# 02-MCU.net
KiCad netlist of a schematic drawn in Altium Designer
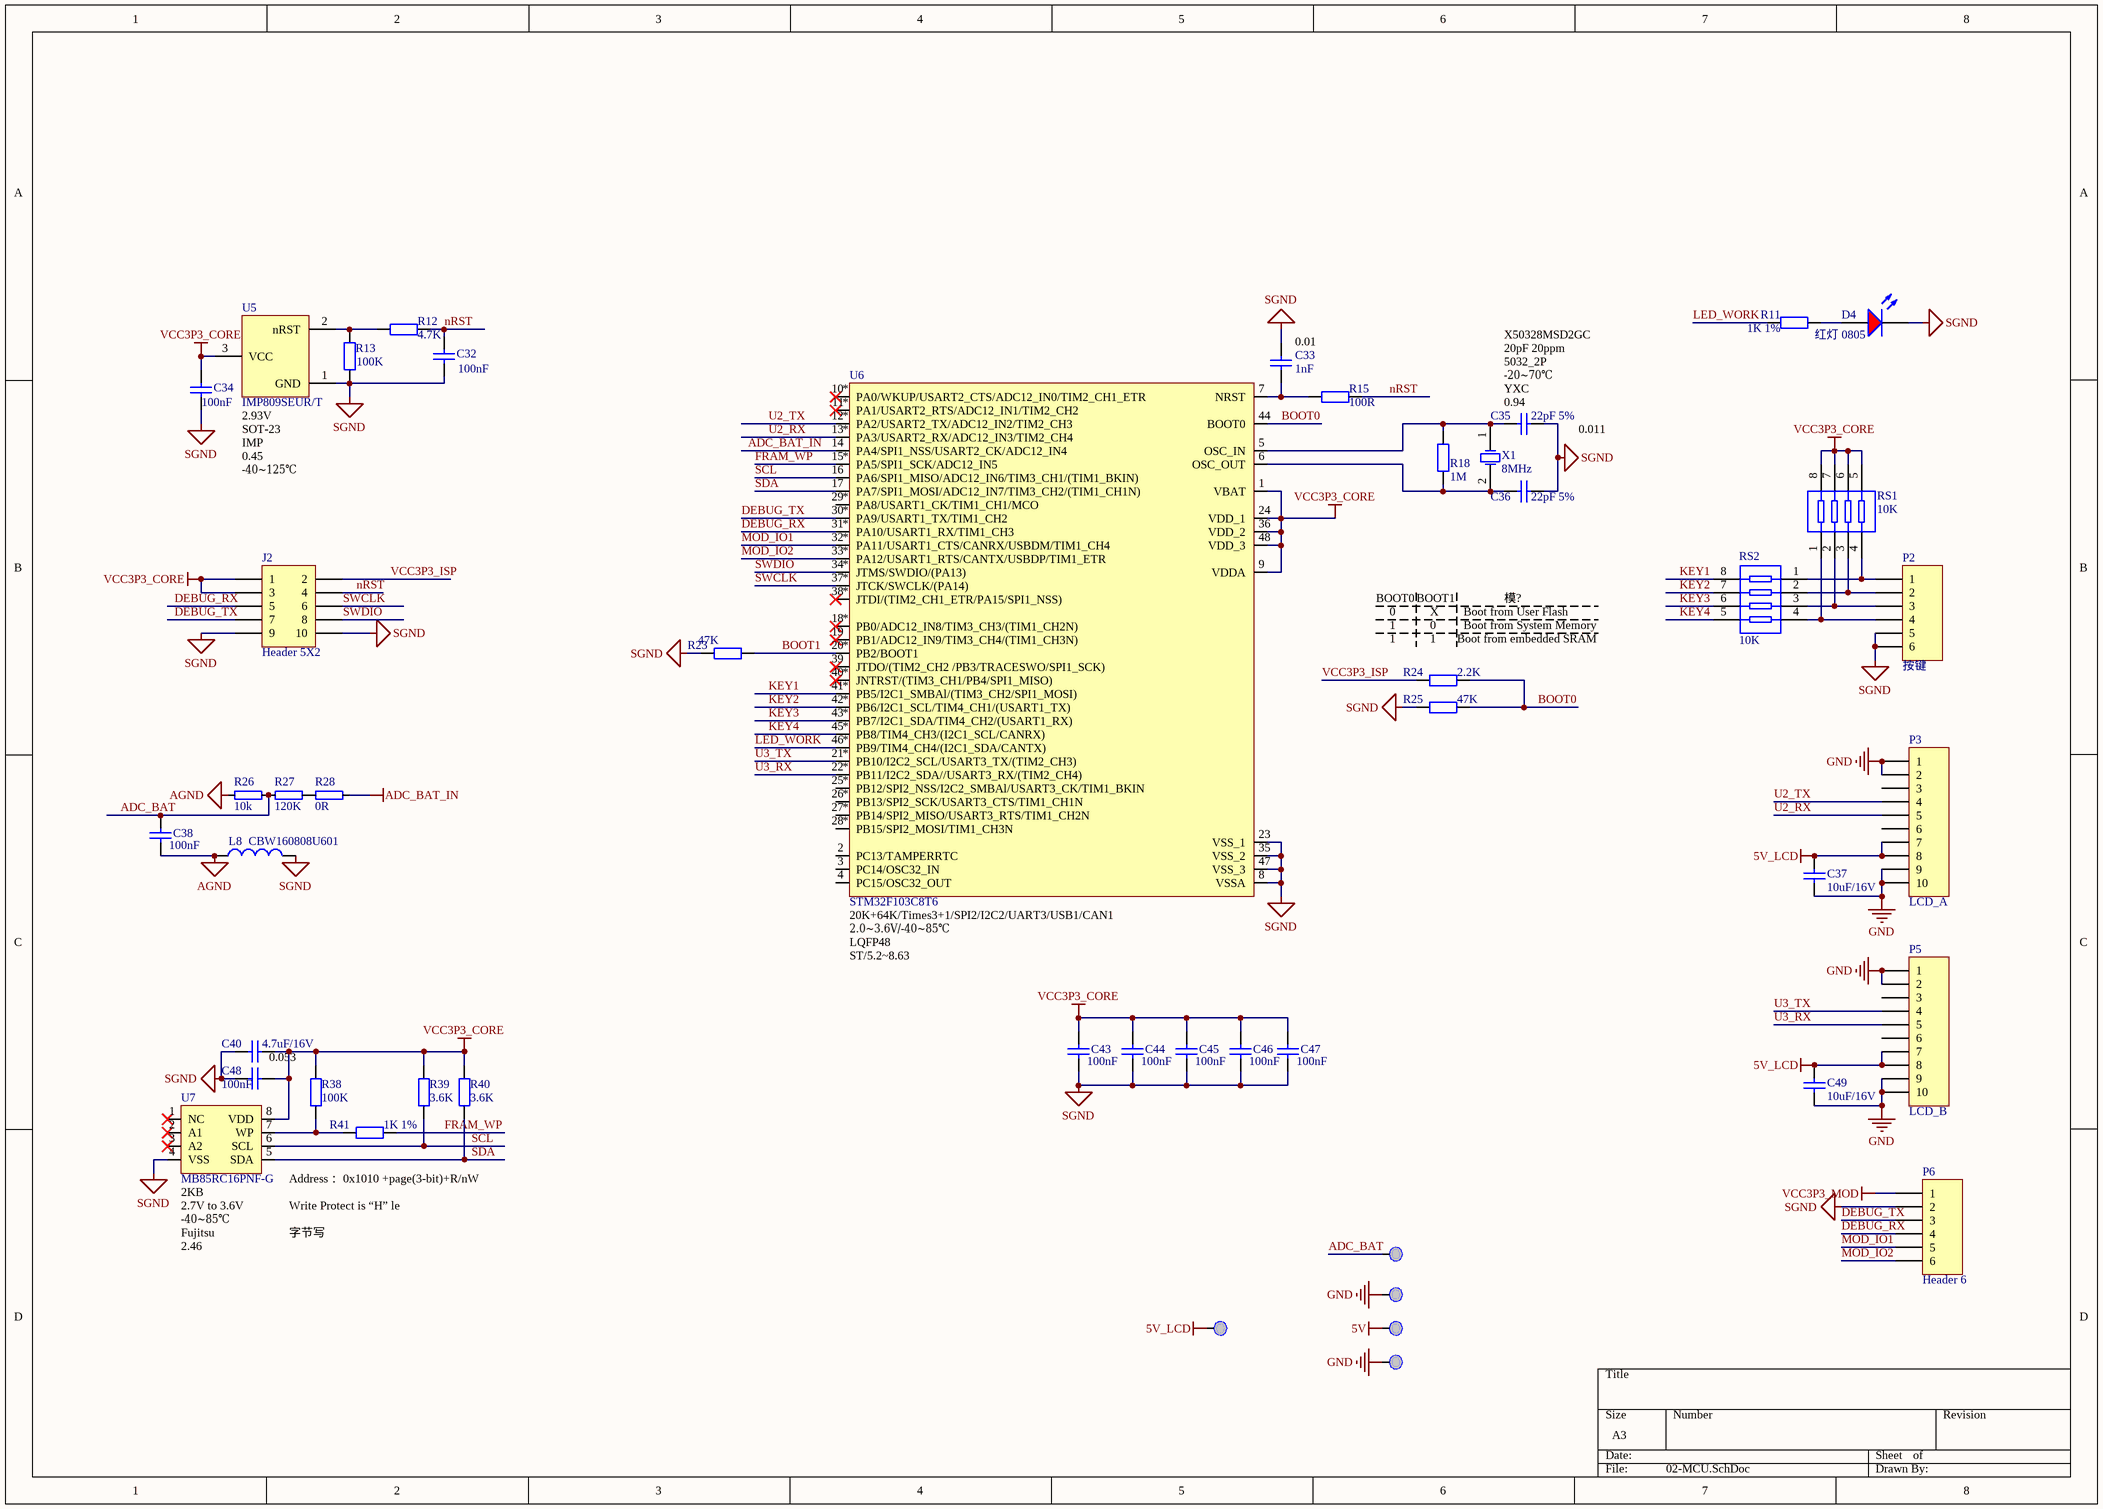
[diagram p0: 02-MCU.SchDoc]

(export (version "E")
  (design (tool "Eeschema 10.0.6"))
  (components
    (comp (ref "C32")
      (value "100nF")
      (footprint "C1608(CC0603)")
      (description "Capacitor")
      (fields (field (name "PUBLISHER") "Altium Limited"))
      (libsource (lib "Miscellaneous Devices") (part "Cap"))
    )
    (comp (ref "C33")
      (value "1nF")
      (footprint "C1608(CC0603)")
      (description "Capacitor")
      (fields (field (name "PUBLISHER") "Altium Limited"))
      (libsource (lib "Miscellaneous Devices") (part "Cap"))
    )
    (comp (ref "C34")
      (value "100nF")
      (footprint "C1608(CC0603)")
      (description "Capacitor")
      (fields (field (name "PUBLISHER") "Altium Limited"))
      (libsource (lib "Miscellaneous Devices") (part "Cap"))
    )
    (comp (ref "C35")
      (value "22pF 5%")
      (footprint "C1608(CC0603)")
      (description "Capacitor")
      (fields (field (name "PUBLISHER") "Altium Limited"))
      (libsource (lib "") (part "Cap_1"))
    )
    (comp (ref "C36")
      (value "22pF 5%")
      (footprint "C1608(CC0603)")
      (description "Capacitor")
      (fields (field (name "PUBLISHER") "Altium Limited"))
      (libsource (lib "") (part "Cap_1"))
    )
    (comp (ref "C37")
      (value "10uF/16V")
      (footprint "C2012(CC0805)")
      (description "Capacitor")
      (fields (field (name "PUBLISHER") "Altium Limited"))
      (libsource (lib "Miscellaneous Devices") (part "Cap"))
    )
    (comp (ref "C38")
      (value "100nF")
      (footprint "C1608(CC0603)")
      (description "Capacitor")
      (fields (field (name "PUBLISHER") "Altium Limited"))
      (libsource (lib "Miscellaneous Devices") (part "Cap"))
    )
    (comp (ref "C40")
      (value "4.7uF/16V")
      (footprint "C1608(CC0603)")
      (description "Capacitor")
      (fields (field (name "PUBLISHER") "Altium Limited"))
      (libsource (lib "Miscellaneous Devices") (part "Cap"))
    )
    (comp (ref "C43")
      (value "100nF")
      (footprint "C1608(CC0603)")
      (description "Capacitor")
      (fields (field (name "PUBLISHER") "Altium Limited"))
      (libsource (lib "Miscellaneous Devices") (part "Cap"))
    )
    (comp (ref "C44")
      (value "100nF")
      (footprint "C1608(CC0603)")
      (description "Capacitor")
      (fields (field (name "PUBLISHER") "Altium Limited"))
      (libsource (lib "Miscellaneous Devices") (part "Cap"))
    )
    (comp (ref "C45")
      (value "100nF")
      (footprint "C1608(CC0603)")
      (description "Capacitor")
      (fields (field (name "PUBLISHER") "Altium Limited"))
      (libsource (lib "Miscellaneous Devices") (part "Cap"))
    )
    (comp (ref "C46")
      (value "100nF")
      (footprint "C1608(CC0603)")
      (description "Capacitor")
      (fields (field (name "PUBLISHER") "Altium Limited"))
      (libsource (lib "Miscellaneous Devices") (part "Cap"))
    )
    (comp (ref "C47")
      (value "100nF")
      (footprint "C1608(CC0603)")
      (description "Capacitor")
      (fields (field (name "PUBLISHER") "Altium Limited"))
      (libsource (lib "Miscellaneous Devices") (part "Cap"))
    )
    (comp (ref "C48")
      (value "100nF")
      (footprint "C1608(CC0603)")
      (description "Capacitor")
      (fields (field (name "PUBLISHER") "Altium Limited"))
      (libsource (lib "") (part "Cap_1"))
    )
    (comp (ref "C49")
      (value "10uF/16V")
      (footprint "C2012(CC0805)")
      (description "Capacitor")
      (fields (field (name "PUBLISHER") "Altium Limited"))
      (libsource (lib "Miscellaneous Devices") (part "Cap"))
    )
    (comp (ref "D4")
      (value "红灯 0805")
      (footprint "LC-0603_LED_S1")
      (description "发光二极管")
      (libsource (lib "Miscellaneous Devices LC") (part "0805 红灯"))
    )
    (comp (ref "J2")
      (value "Header 5X2")
      (footprint "HDR2X5")
      (description "Header, 5-Pin, Dual row")
      (fields (field (name "PUBLISHER") "Altium Limited"))
      (libsource (lib "Miscellaneous Connectors") (part "Header 5X2"))
    )
    (comp (ref "L8")
      (value "CBW160808U601")
      (footprint "C1608(CC0603)")
      (description "Inductor")
      (fields (field (name "PUBLISHER") "Altium Limited"))
      (libsource (lib "Miscellaneous Devices") (part "Inductor"))
    )
    (comp (ref "P2")
      (value "按键")
      (footprint "PH-6A")
      (description "Header, 6-Pin")
      (fields (field (name "PUBLISHER") "Altium Limited"))
      (libsource (lib "Miscellaneous Connectors") (part "Header 6"))
    )
    (comp (ref "P3")
      (value "LCD_A")
      (footprint "2mm-header_SMT")
      (description "Header, 10-Pin")
      (fields (field (name "PUBLISHER") "Altium Limited"))
      (libsource (lib "Miscellaneous Connectors") (part "Header 10"))
    )
    (comp (ref "P5")
      (value "LCD_B")
      (footprint "2mm-header_SMT")
      (description "Header, 10-Pin")
      (fields (field (name "PUBLISHER") "Altium Limited"))
      (libsource (lib "Miscellaneous Connectors") (part "Header 10"))
    )
    (comp (ref "P6")
      (value "Header 6")
      (footprint "HDR1X6")
      (description "Header, 6-Pin")
      (fields (field (name "PUBLISHER") "Altium Limited"))
      (libsource (lib "Miscellaneous Connectors") (part "Header 6"))
    )
    (comp (ref "R11")
      (value "1K 1%")
      (footprint "C1608(CC0603)")
      (description "Resistor")
      (fields (field (name "PUBLISHER") "Altium Limited"))
      (libsource (lib "") (part "Res2_1"))
    )
    (comp (ref "R12")
      (value "4.7K")
      (footprint "C1608(CC0603)")
      (description "Resistor")
      (fields (field (name "PUBLISHER") "Altium Limited"))
      (libsource (lib "") (part "Res2_1"))
    )
    (comp (ref "R13")
      (value "100K")
      (footprint "C1608(CC0603)")
      (description "Resistor")
      (fields (field (name "PUBLISHER") "Altium Limited"))
      (libsource (lib "Miscellaneous Devices") (part "Res2"))
    )
    (comp (ref "R15")
      (value "100R")
      (footprint "C1608(CC0603)")
      (description "Resistor")
      (fields (field (name "PUBLISHER") "Altium Limited"))
      (libsource (lib "") (part "Res2_1"))
    )
    (comp (ref "R18")
      (value "1M")
      (footprint "C1608(CC0603)")
      (description "Resistor")
      (fields (field (name "PUBLISHER") "Altium Limited"))
      (libsource (lib "") (part "Res2_2"))
    )
    (comp (ref "R23")
      (value "47K")
      (footprint "C1608(CC0603)")
      (description "Resistor")
      (fields (field (name "PUBLISHER") "Altium Limited"))
      (libsource (lib "") (part "Res2_1"))
    )
    (comp (ref "R24")
      (value "2.2K")
      (footprint "C1608(CC0603)")
      (description "Resistor")
      (fields (field (name "PUBLISHER") "Altium Limited"))
      (libsource (lib "") (part "Res2_3"))
    )
    (comp (ref "R25")
      (value "47K")
      (footprint "C1608(CC0603)")
      (description "Resistor")
      (fields (field (name "PUBLISHER") "Altium Limited"))
      (libsource (lib "") (part "Res2_1"))
    )
    (comp (ref "R26") (value "10k") (footprint "C1608(CC0603)") (libsource (lib "SCHS") (part "RES5")))
    (comp (ref "R27") (value "120K") (footprint "C1608(CC0603)") (libsource (lib "SCHS") (part "RES5")))
    (comp (ref "R28") (value "0R") (footprint "C1608(CC0603)") (libsource (lib "SCHS") (part "RES5")))
    (comp (ref "R38")
      (value "100K")
      (footprint "C1608(CC0603)")
      (description "Resistor")
      (fields (field (name "PUBLISHER") "Altium Limited"))
      (libsource (lib "Miscellaneous Devices") (part "Res2"))
    )
    (comp (ref "R39")
      (value "3.6K")
      (footprint "C1608(CC0603)")
      (description "Resistor")
      (fields (field (name "PUBLISHER") "Altium Limited"))
      (libsource (lib "Miscellaneous Devices") (part "Res2"))
    )
    (comp (ref "R40")
      (value "3.6K")
      (footprint "C1608(CC0603)")
      (description "Resistor")
      (fields (field (name "PUBLISHER") "Altium Limited"))
      (libsource (lib "Miscellaneous Devices") (part "Res2"))
    )
    (comp (ref "R41")
      (value "1K 1%")
      (footprint "C1608(CC0603)")
      (description "Resistor")
      (fields (field (name "PUBLISHER") "Altium Limited"))
      (libsource (lib "") (part "Res2_4"))
    )
    (comp (ref "RS1")
      (value "10K")
      (footprint "LC-0603_Rx4")
      (description "贴片排阻")
      (libsource (lib "Miscellaneous Devices LC") (part "0603*4  10KΩ (103) 5%"))
    )
    (comp (ref "RS2")
      (value "10K")
      (footprint "LC-0603_Rx4")
      (description "贴片排阻")
      (libsource (lib "Miscellaneous Devices LC") (part "0603*4  10KΩ (103) 5%"))
    )
    (comp (ref "T13") (value "TP") (footprint "M2铜柱") (libsource (lib "个人") (part "TP")))
    (comp (ref "T15") (value "TP") (footprint "M2铜柱") (libsource (lib "个人") (part "TP")))
    (comp (ref "T16") (value "TP") (footprint "M2铜柱") (libsource (lib "个人") (part "TP")))
    (comp (ref "T18") (value "TP") (footprint "M2铜柱") (libsource (lib "个人") (part "TP")))
    (comp (ref "T20") (value "TP") (footprint "M2铜柱") (libsource (lib "个人") (part "TP")))
    (comp (ref "U5")
      (value "IMP809SEUR/T")
      (footprint "SOT-23")
      (libsource (lib "Schlibsxw") (part "CAT810"))
    )
    (comp (ref "U6")
      (value "STM32F103C8T6")
      (footprint "LC-LQFP-48_7x7x05P")
      (libsource (lib "Schlibsxw") (part "STM32F103Cx"))
    )
    (comp (ref "U7")
      (value "MB85RC16PNF-G")
      (footprint "LC-SOP-8_150mil")
      (libsource (lib "Schlibsxw") (part "FM24CL04"))
    )
    (comp (ref "X1")
      (value "8MHz")
      (footprint "XTAL-5032")
      (description "Crystal Oscillator")
      (fields (field (name "PUBLISHER") "Altium Limited"))
      (libsource (lib "Miscellaneous Devices") (part "XTAL"))
    )
  )
  (nets
    (net (code "1") (name "/ADC_BAT") (class "Default")
      (node (ref "C38") (pin "1") (pinfunction "1_1") (pintype "passive"))
      (node (ref "R26") (pin "1") (pintype "passive"))
      (node (ref "R27") (pin "2") (pintype "passive"))
      (node (ref "T13") (pin "1") (pintype "passive"))
    )
    (net (code "2") (name "/BOOT0") (class "Default")
      (node (ref "R24") (pin "1") (pinfunction "1_1") (pintype "passive"))
      (node (ref "R25") (pin "2") (pinfunction "2_2") (pintype "passive"))
      (node (ref "U6") (pin "44") (pinfunction "BOOT0_44") (pintype "passive"))
    )
    (net (code "3") (name "/BOOT1") (class "Default")
      (node (ref "R23") (pin "2") (pinfunction "2_2") (pintype "passive"))
      (node (ref "U6") (pin "20") (pinfunction "PB2/BOOT1_20") (pintype "passive"))
    )
    (net (code "4") (name "/DEBUG_RX") (class "Default")
      (node (ref "J2") (pin "5") (pinfunction "5_5") (pintype "passive"))
      (node (ref "P6") (pin "4") (pinfunction "4_4") (pintype "passive"))
      (node (ref "U6") (pin "31") (pinfunction "PA10/USART1_RX/TIM1_CH3_31") (pintype "passive"))
    )
    (net (code "5") (name "/DEBUG_TX") (class "Default")
      (node (ref "J2") (pin "7") (pinfunction "7_7") (pintype "passive"))
      (node (ref "P6") (pin "3") (pinfunction "3_3") (pintype "passive"))
      (node (ref "U6") (pin "30") (pinfunction "PA9/USART1_TX/TIM1_CH2_30") (pintype "passive"))
    )
    (net (code "6") (name "/FRAM_WP") (class "Default")
      (node (ref "R41") (pin "2") (pinfunction "2_2") (pintype "passive"))
      (node (ref "U6") (pin "15") (pinfunction "PA5/SPI1_SCK/ADC12_IN5_15") (pintype "passive"))
    )
    (net (code "7") (name "/KEY1") (class "Default")
      (node (ref "RS2") (pin "8") (pinfunction "8_8") (pintype "passive"))
      (node (ref "U6") (pin "41") (pinfunction "PB5/I2C1_SMBAl/(TIM3_CH2/SPI1_MOSI)_41") (pintype "passive"))
    )
    (net (code "8") (name "/KEY2") (class "Default")
      (node (ref "RS2") (pin "7") (pinfunction "7_7") (pintype "passive"))
      (node (ref "U6") (pin "42") (pinfunction "PB6/I2C1_SCL/TIM4_CH1/(USART1_TX)_42") (pintype "passive"))
    )
    (net (code "9") (name "/KEY3") (class "Default")
      (node (ref "RS2") (pin "6") (pinfunction "6_6") (pintype "passive"))
      (node (ref "U6") (pin "43") (pinfunction "PB7/I2C1_SDA/TIM4_CH2/(USART1_RX)_43") (pintype "passive"))
    )
    (net (code "10") (name "/KEY4") (class "Default")
      (node (ref "RS2") (pin "5") (pinfunction "5_5") (pintype "passive"))
      (node (ref "U6") (pin "45") (pinfunction "PB8/TIM4_CH3/(I2C1_SCL/CANRX)_45") (pintype "passive"))
    )
    (net (code "11") (name "/LED_WORK") (class "Default")
      (node (ref "R11") (pin "1") (pinfunction "1_1") (pintype "passive"))
      (node (ref "U6") (pin "46") (pinfunction "PB9/TIM4_CH4/(I2C1_SDA/CANTX)_46") (pintype "passive"))
    )
    (net (code "12") (name "/MOD_IO1") (class "Default")
      (node (ref "P6") (pin "5") (pinfunction "5_5") (pintype "passive"))
      (node (ref "U6") (pin "32") (pinfunction "PA11/USART1_CTS/CANRX/USBDM/TIM1_CH4_32") (pintype "passive"))
    )
    (net (code "13") (name "/MOD_IO2") (class "Default")
      (node (ref "P6") (pin "6") (pinfunction "6_6") (pintype "passive"))
      (node (ref "U6") (pin "33") (pinfunction "PA12/USART1_RTS/CANTX/USBDP/TIM1_ETR_33") (pintype "passive"))
    )
    (net (code "14") (name "/SCL") (class "Default")
      (node (ref "R39") (pin "1") (pinfunction "1_1") (pintype "passive"))
      (node (ref "U6") (pin "16") (pinfunction "PA6/SPI1_MISO/ADC12_IN6/TIM3_CH1/(TIM1_BKIN)_16") (pintype "passive"))
      (node (ref "U7") (pin "6") (pinfunction "SCL_6") (pintype "passive"))
    )
    (net (code "15") (name "/SDA") (class "Default")
      (node (ref "R40") (pin "1") (pinfunction "1_1") (pintype "passive"))
      (node (ref "U6") (pin "17") (pinfunction "PA7/SPI1_MOSI/ADC12_IN7/TIM3_CH2/(TIM1_CH1N)_17") (pintype "passive"))
      (node (ref "U7") (pin "5") (pinfunction "SDA_5") (pintype "passive"))
    )
    (net (code "16") (name "/SWCLK") (class "Default")
      (node (ref "J2") (pin "6") (pinfunction "6_6") (pintype "passive"))
      (node (ref "U6") (pin "37") (pinfunction "JTCK/SWCLK/(PA14)_37") (pintype "passive"))
    )
    (net (code "17") (name "/SWDIO") (class "Default")
      (node (ref "J2") (pin "8") (pinfunction "8_8") (pintype "passive"))
      (node (ref "U6") (pin "34") (pinfunction "JTMS/SWDIO/(PA13)_34") (pintype "passive"))
    )
    (net (code "18") (name "/U2_RX") (class "Default")
      (node (ref "P3") (pin "5") (pinfunction "5_5") (pintype "passive"))
      (node (ref "U6") (pin "13") (pinfunction "PA3/USART2_RX/ADC12_IN3/TIM2_CH4_13") (pintype "passive"))
    )
    (net (code "19") (name "/U2_TX") (class "Default")
      (node (ref "P3") (pin "4") (pinfunction "4_4") (pintype "passive"))
      (node (ref "U6") (pin "12") (pinfunction "PA2/USART2_TX/ADC12_IN2/TIM2_CH3_12") (pintype "passive"))
    )
    (net (code "20") (name "/U3_RX") (class "Default")
      (node (ref "P5") (pin "5") (pinfunction "5_5") (pintype "passive"))
      (node (ref "U6") (pin "22") (pinfunction "PB11/I2C2_SDA//USART3_RX/(TIM2_CH4)_22") (pintype "passive"))
    )
    (net (code "21") (name "/U3_TX") (class "Default")
      (node (ref "P5") (pin "4") (pinfunction "4_4") (pintype "passive"))
      (node (ref "U6") (pin "21") (pinfunction "PB10/I2C2_SCL/USART3_TX/(TIM2_CH3)_21") (pintype "passive"))
    )
    (net (code "22") (name "/VCC3P3_ISP") (class "Default")
      (node (ref "J2") (pin "2") (pinfunction "2_2") (pintype "passive"))
      (node (ref "R24") (pin "2") (pinfunction "2_2") (pintype "passive"))
    )
    (net (code "23") (name "/nRST") (class "Default")
      (node (ref "C32") (pin "1") (pinfunction "1_1") (pintype "passive"))
      (node (ref "J2") (pin "4") (pinfunction "4_4") (pintype "passive"))
      (node (ref "R12") (pin "2") (pinfunction "2_2") (pintype "passive"))
      (node (ref "R15") (pin "2") (pinfunction "2_2") (pintype "passive"))
    )
    (net (code "24") (name "5V") (class "Default") (node (ref "T15") (pin "1") (pintype "passive")))
    (net (code "25") (name "5V_LCD") (class "Default")
      (node (ref "C37") (pin "2") (pinfunction "2_2") (pintype "passive"))
      (node (ref "C49") (pin "2") (pinfunction "2_2") (pintype "passive"))
      (node (ref "P3") (pin "7") (pinfunction "7_7") (pintype "passive"))
      (node (ref "P3") (pin "8") (pinfunction "8_8") (pintype "passive"))
      (node (ref "P5") (pin "7") (pinfunction "7_7") (pintype "passive"))
      (node (ref "P5") (pin "8") (pinfunction "8_8") (pintype "passive"))
      (node (ref "T16") (pin "1") (pintype "passive"))
    )
    (net (code "26") (name "ADC_BAT_IN") (class "Default")
      (node (ref "R28") (pin "1") (pintype "passive"))
      (node (ref "U6") (pin "14") (pinfunction "PA4/SPI1_NSS/USART2_CK/ADC12_IN4_14") (pintype "passive"))
    )
    (net (code "27") (name "AGND") (class "Default")
      (node (ref "C38") (pin "2") (pinfunction "2_2") (pintype "passive"))
      (node (ref "L8") (pin "1") (pinfunction "1_1") (pintype "passive"))
      (node (ref "R26") (pin "2") (pintype "passive"))
    )
    (net (code "28") (name "GND") (class "Default")
      (node (ref "C37") (pin "1") (pinfunction "1_1") (pintype "passive"))
      (node (ref "C49") (pin "1") (pinfunction "1_1") (pintype "passive"))
      (node (ref "P3") (pin "1") (pinfunction "1_1") (pintype "passive"))
      (node (ref "P3") (pin "10") (pinfunction "10_10") (pintype "passive"))
      (node (ref "P3") (pin "2") (pinfunction "2_2") (pintype "passive"))
      (node (ref "P3") (pin "9") (pinfunction "9_9") (pintype "passive"))
      (node (ref "P5") (pin "1") (pinfunction "1_1") (pintype "passive"))
      (node (ref "P5") (pin "10") (pinfunction "10_10") (pintype "passive"))
      (node (ref "P5") (pin "2") (pinfunction "2_2") (pintype "passive"))
      (node (ref "P5") (pin "9") (pinfunction "9_9") (pintype "passive"))
      (node (ref "T18") (pin "1") (pintype "passive"))
      (node (ref "T20") (pin "1") (pintype "passive"))
    )
    (net (code "29") (name "Net-(D4-PadA)") (class "Default")
      (node (ref "D4") (pin "A") (pinfunction "A_A") (pintype "passive"))
      (node (ref "R11") (pin "2") (pinfunction "2_2") (pintype "passive"))
    )
    (net (code "30") (name "Net-(P2-Pad1)") (class "Default")
      (node (ref "P2") (pin "1") (pinfunction "1_1") (pintype "passive"))
      (node (ref "RS1") (pin "4") (pinfunction "4_4") (pintype "passive"))
      (node (ref "RS2") (pin "1") (pinfunction "1_1") (pintype "passive"))
    )
    (net (code "31") (name "Net-(P2-Pad2)") (class "Default")
      (node (ref "P2") (pin "2") (pinfunction "2_2") (pintype "passive"))
      (node (ref "RS1") (pin "3") (pinfunction "3_3") (pintype "passive"))
      (node (ref "RS2") (pin "2") (pinfunction "2_2") (pintype "passive"))
    )
    (net (code "32") (name "Net-(P2-Pad3)") (class "Default")
      (node (ref "P2") (pin "3") (pinfunction "3_3") (pintype "passive"))
      (node (ref "RS1") (pin "2") (pinfunction "2_2") (pintype "passive"))
      (node (ref "RS2") (pin "3") (pinfunction "3_3") (pintype "passive"))
    )
    (net (code "33") (name "Net-(P2-Pad4)") (class "Default")
      (node (ref "P2") (pin "4") (pinfunction "4_4") (pintype "passive"))
      (node (ref "RS1") (pin "1") (pinfunction "1_1") (pintype "passive"))
      (node (ref "RS2") (pin "4") (pinfunction "4_4") (pintype "passive"))
    )
    (net (code "34") (name "Net-(R27-Pad1)") (class "Default")
      (node (ref "R27") (pin "1") (pintype "passive"))
      (node (ref "R28") (pin "2") (pintype "passive"))
    )
    (net (code "35") (name "Net-(U5-nRST)") (class "Default")
      (node (ref "R12") (pin "1") (pinfunction "1_1") (pintype "passive"))
      (node (ref "R13") (pin "2") (pinfunction "2_2") (pintype "passive"))
      (node (ref "U5") (pin "2") (pinfunction "nRST_2") (pintype "passive"))
    )
    (net (code "36") (name "Net-(U6-NRST)") (class "Default")
      (node (ref "C33") (pin "1") (pinfunction "1_1") (pintype "passive"))
      (node (ref "R15") (pin "1") (pinfunction "1_1") (pintype "passive"))
      (node (ref "U6") (pin "7") (pinfunction "NRST_7") (pintype "passive"))
    )
    (net (code "37") (name "Net-(U6-OSC_IN)") (class "Default")
      (node (ref "C35") (pin "2") (pinfunction "2_2") (pintype "passive"))
      (node (ref "R18") (pin "1") (pinfunction "1_1") (pintype "passive"))
      (node (ref "U6") (pin "5") (pinfunction "OSC_IN_5") (pintype "passive"))
      (node (ref "X1") (pin "1") (pinfunction "OSC1_1") (pintype "passive"))
    )
    (net (code "38") (name "Net-(U6-OSC_OUT)") (class "Default")
      (node (ref "C36") (pin "2") (pinfunction "2_2") (pintype "passive"))
      (node (ref "R18") (pin "2") (pinfunction "2_2") (pintype "passive"))
      (node (ref "U6") (pin "6") (pinfunction "OSC_OUT_6") (pintype "passive"))
      (node (ref "X1") (pin "2") (pinfunction "OSC2_2") (pintype "passive"))
    )
    (net (code "39") (name "Net-(U7-WP)") (class "Default")
      (node (ref "R38") (pin "1") (pinfunction "1_1") (pintype "passive"))
      (node (ref "R41") (pin "1") (pinfunction "1_1") (pintype "passive"))
      (node (ref "U7") (pin "7") (pinfunction "WP_7") (pintype "passive"))
    )
    (net (code "40") (name "SGND") (class "Default")
      (node (ref "C32") (pin "2") (pinfunction "2_2") (pintype "passive"))
      (node (ref "C33") (pin "2") (pinfunction "2_2") (pintype "passive"))
      (node (ref "C34") (pin "2") (pinfunction "2_2") (pintype "passive"))
      (node (ref "C35") (pin "1") (pinfunction "1_1") (pintype "passive"))
      (node (ref "C36") (pin "1") (pinfunction "1_1") (pintype "passive"))
      (node (ref "C40") (pin "2") (pinfunction "2_2") (pintype "passive"))
      (node (ref "C43") (pin "2") (pinfunction "2_2") (pintype "passive"))
      (node (ref "C44") (pin "2") (pinfunction "2_2") (pintype "passive"))
      (node (ref "C45") (pin "2") (pinfunction "2_2") (pintype "passive"))
      (node (ref "C46") (pin "2") (pinfunction "2_2") (pintype "passive"))
      (node (ref "C47") (pin "2") (pinfunction "2_2") (pintype "passive"))
      (node (ref "C48") (pin "1") (pinfunction "1_1") (pintype "passive"))
      (node (ref "D4") (pin "K") (pinfunction "K_K") (pintype "passive"))
      (node (ref "J2") (pin "10") (pinfunction "10_10") (pintype "passive"))
      (node (ref "J2") (pin "9") (pinfunction "9_9") (pintype "passive"))
      (node (ref "L8") (pin "2") (pinfunction "2_2") (pintype "passive"))
      (node (ref "P2") (pin "5") (pinfunction "5_5") (pintype "passive"))
      (node (ref "P2") (pin "6") (pinfunction "6_6") (pintype "passive"))
      (node (ref "P6") (pin "2") (pinfunction "2_2") (pintype "passive"))
      (node (ref "R13") (pin "1") (pinfunction "1_1") (pintype "passive"))
      (node (ref "R23") (pin "1") (pinfunction "1_1") (pintype "passive"))
      (node (ref "R25") (pin "1") (pinfunction "1_1") (pintype "passive"))
      (node (ref "U5") (pin "1") (pinfunction "GND_1") (pintype "passive"))
      (node (ref "U6") (pin "23") (pinfunction "VSS_1_23") (pintype "passive"))
      (node (ref "U6") (pin "35") (pinfunction "VSS_2_35") (pintype "passive"))
      (node (ref "U6") (pin "47") (pinfunction "VSS_3_47") (pintype "passive"))
      (node (ref "U6") (pin "8") (pinfunction "VSSA_8") (pintype "passive"))
      (node (ref "U7") (pin "4") (pinfunction "VSS_4") (pintype "passive"))
    )
    (net (code "41") (name "VCC3P3_CORE") (class "Default")
      (node (ref "C34") (pin "1") (pinfunction "1_1") (pintype "passive"))
      (node (ref "C40") (pin "1") (pinfunction "1_1") (pintype "passive"))
      (node (ref "C43") (pin "1") (pinfunction "1_1") (pintype "passive"))
      (node (ref "C44") (pin "1") (pinfunction "1_1") (pintype "passive"))
      (node (ref "C45") (pin "1") (pinfunction "1_1") (pintype "passive"))
      (node (ref "C46") (pin "1") (pinfunction "1_1") (pintype "passive"))
      (node (ref "C47") (pin "1") (pinfunction "1_1") (pintype "passive"))
      (node (ref "C48") (pin "2") (pinfunction "2_2") (pintype "passive"))
      (node (ref "J2") (pin "1") (pinfunction "1_1") (pintype "passive"))
      (node (ref "J2") (pin "3") (pinfunction "3_3") (pintype "passive"))
      (node (ref "R38") (pin "2") (pinfunction "2_2") (pintype "passive"))
      (node (ref "R39") (pin "2") (pinfunction "2_2") (pintype "passive"))
      (node (ref "R40") (pin "2") (pinfunction "2_2") (pintype "passive"))
      (node (ref "RS1") (pin "5") (pinfunction "5_5") (pintype "passive"))
      (node (ref "RS1") (pin "6") (pinfunction "6_6") (pintype "passive"))
      (node (ref "RS1") (pin "7") (pinfunction "7_7") (pintype "passive"))
      (node (ref "RS1") (pin "8") (pinfunction "8_8") (pintype "passive"))
      (node (ref "U5") (pin "3") (pinfunction "VCC_3") (pintype "passive"))
      (node (ref "U6") (pin "1") (pinfunction "VBAT_1") (pintype "passive"))
      (node (ref "U6") (pin "24") (pinfunction "VDD_1_24") (pintype "passive"))
      (node (ref "U6") (pin "36") (pinfunction "VDD_2_36") (pintype "passive"))
      (node (ref "U6") (pin "48") (pinfunction "VDD_3_48") (pintype "passive"))
      (node (ref "U6") (pin "9") (pinfunction "VDDA_9") (pintype "passive"))
      (node (ref "U7") (pin "8") (pinfunction "VDD_8") (pintype "passive"))
    )
    (net (code "42") (name "VCC3P3_MOD") (class "Default")
      (node (ref "P6") (pin "1") (pinfunction "1_1") (pintype "passive"))
    )
    (net (code "43") (name "unconnected-(P3-Pad3)") (class "Default")
      (node (ref "P3") (pin "3") (pinfunction "3_3") (pintype "passive"))
    )
    (net (code "44") (name "unconnected-(P3-Pad6)") (class "Default")
      (node (ref "P3") (pin "6") (pinfunction "6_6") (pintype "passive"))
    )
    (net (code "45") (name "unconnected-(P5-Pad3)") (class "Default")
      (node (ref "P5") (pin "3") (pinfunction "3_3") (pintype "passive"))
    )
    (net (code "46") (name "unconnected-(P5-Pad6)") (class "Default")
      (node (ref "P5") (pin "6") (pinfunction "6_6") (pintype "passive"))
    )
    (net (code "47") (name "unconnected-(U6-JNTRST{slash}(TIM3_CH1{slash}PB4{slash}SPI1_MISO)-Pad40)") (class "Default")
      (node (ref "U6") (pin "40") (pinfunction "JNTRST/(TIM3_CH1/PB4/SPI1_MISO)_40") (pintype "passive+no_connect"))
    )
    (net (code "48") (name "unconnected-(U6-JTDI{slash}(TIM2_CH1_ETR{slash}PA15{slash}SPI1_NSS)-Pad38)") (class "Default")
      (node (ref "U6") (pin "38") (pinfunction "JTDI/(TIM2_CH1_ETR/PA15/SPI1_NSS)_38") (pintype "passive+no_connect"))
    )
    (net (code "49") (name "unconnected-(U6-JTDO{slash}(TIM2_CH2_{slash}PB3{slash}TRACESWO{slash}SPI1_SCK)-Pad39)") (class "Default")
      (node (ref "U6") (pin "39") (pinfunction "JTDO/(TIM2_CH2_/PB3/TRACESWO/SPI1_SCK)_39") (pintype "passive+no_connect"))
    )
    (net (code "50") (name "unconnected-(U6-PA0{slash}WKUP{slash}USART2_CTS{slash}ADC12_IN0{slash}TIM2_CH1_ETR-Pad10)") (class "Default")
      (node (ref "U6") (pin "10") (pinfunction "PA0/WKUP/USART2_CTS/ADC12_IN0/TIM2_CH1_ETR_10") (pintype "passive+no_connect"))
    )
    (net (code "51") (name "unconnected-(U6-PA1{slash}USART2_RTS{slash}ADC12_IN1{slash}TIM2_CH2-Pad11)") (class "Default")
      (node (ref "U6") (pin "11") (pinfunction "PA1/USART2_RTS/ADC12_IN1/TIM2_CH2_11") (pintype "passive+no_connect"))
    )
    (net (code "52") (name "unconnected-(U6-PA8{slash}USART1_CK{slash}TIM1_CH1{slash}MCO-Pad29)") (class "Default")
      (node (ref "U6") (pin "29") (pinfunction "PA8/USART1_CK/TIM1_CH1/MCO_29") (pintype "passive"))
    )
    (net (code "53") (name "unconnected-(U6-PB0{slash}ADC12_IN8{slash}TIM3_CH3{slash}(TIM1_CH2N)-Pad18)") (class "Default")
      (node (ref "U6") (pin "18") (pinfunction "PB0/ADC12_IN8/TIM3_CH3/(TIM1_CH2N)_18") (pintype "passive+no_connect"))
    )
    (net (code "54") (name "unconnected-(U6-PB1{slash}ADC12_IN9{slash}TIM3_CH4{slash}(TIM1_CH3N)-Pad19)") (class "Default")
      (node (ref "U6") (pin "19") (pinfunction "PB1/ADC12_IN9/TIM3_CH4/(TIM1_CH3N)_19") (pintype "passive+no_connect"))
    )
    (net (code "55") (name "unconnected-(U6-PB12{slash}SPI2_NSS{slash}I2C2_SMBAl{slash}USART3_CK{slash}TIM1_BKIN-Pad25)") (class "Default")
      (node (ref "U6") (pin "25") (pinfunction "PB12/SPI2_NSS/I2C2_SMBAl/USART3_CK/TIM1_BKIN_25") (pintype "passive"))
    )
    (net (code "56") (name "unconnected-(U6-PB13{slash}SPI2_SCK{slash}USART3_CTS{slash}TIM1_CH1N-Pad26)") (class "Default")
      (node (ref "U6") (pin "26") (pinfunction "PB13/SPI2_SCK/USART3_CTS/TIM1_CH1N_26") (pintype "passive"))
    )
    (net (code "57") (name "unconnected-(U6-PB14{slash}SPI2_MISO{slash}USART3_RTS{slash}TIM1_CH2N-Pad27)") (class "Default")
      (node (ref "U6") (pin "27") (pinfunction "PB14/SPI2_MISO/USART3_RTS/TIM1_CH2N_27") (pintype "passive"))
    )
    (net (code "58") (name "unconnected-(U6-PB15{slash}SPI2_MOSI{slash}TIM1_CH3N-Pad28)") (class "Default")
      (node (ref "U6") (pin "28") (pinfunction "PB15/SPI2_MOSI/TIM1_CH3N_28") (pintype "passive"))
    )
    (net (code "59") (name "unconnected-(U6-PC13{slash}TAMPERRTC-Pad2)") (class "Default")
      (node (ref "U6") (pin "2") (pinfunction "PC13/TAMPERRTC_2") (pintype "passive"))
    )
    (net (code "60") (name "unconnected-(U6-PC14{slash}OSC32_IN-Pad3)") (class "Default")
      (node (ref "U6") (pin "3") (pinfunction "PC14/OSC32_IN_3") (pintype "passive"))
    )
    (net (code "61") (name "unconnected-(U6-PC15{slash}OSC32_OUT-Pad4)") (class "Default")
      (node (ref "U6") (pin "4") (pinfunction "PC15/OSC32_OUT_4") (pintype "passive"))
    )
    (net (code "62") (name "unconnected-(U7-A1-Pad2)") (class "Default")
      (node (ref "U7") (pin "2") (pinfunction "A1_2") (pintype "passive+no_connect"))
    )
    (net (code "63") (name "unconnected-(U7-A2-Pad3)") (class "Default")
      (node (ref "U7") (pin "3") (pinfunction "A2_3") (pintype "passive+no_connect"))
    )
    (net (code "64") (name "unconnected-(U7-NC-Pad1)") (class "Default")
      (node (ref "U7") (pin "1") (pinfunction "NC_1") (pintype "passive+no_connect"))
    )
  )
)
